# LowduinoSMD.net
KiCad netlist of a schematic drawn in EAGLE
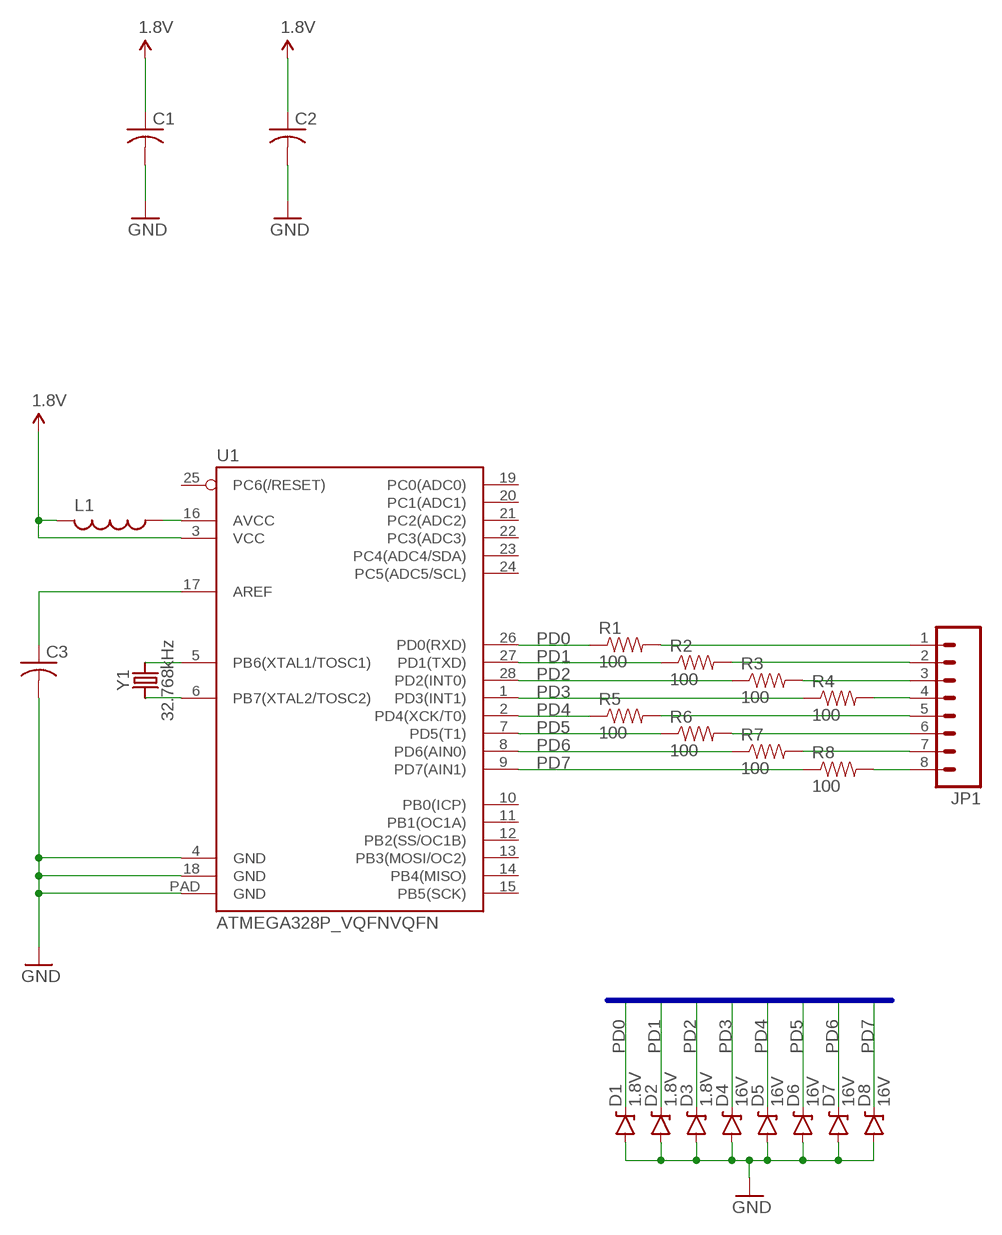
[diagram p0: schematic, sheet 1]

(export (version "E")
  (design (tool "Eeschema 10.0.6"))
  (components
    (comp (ref "C1")
      (value "C-USC0201")
      (footprint "eagle-import:C0201")
      (libsource (lib "eagle-import") (part "C-USC0201"))
    )
    (comp (ref "C2")
      (value "C-USC0402")
      (footprint "eagle-import:C0402")
      (libsource (lib "eagle-import") (part "C-USC0402"))
    )
    (comp (ref "C3")
      (value "C-USC0201")
      (footprint "eagle-import:C0201")
      (libsource (lib "eagle-import") (part "C-USC0201"))
    )
    (comp (ref "D1")
      (value "1.8V")
      (footprint "eagle-import:SOD-123")
      (libsource (lib "eagle-import") (part "DIODE-ZENER16V"))
    )
    (comp (ref "D2")
      (value "1.8V")
      (footprint "eagle-import:SOD-123")
      (libsource (lib "eagle-import") (part "DIODE-ZENER16V"))
    )
    (comp (ref "D3")
      (value "1.8V")
      (footprint "eagle-import:SOD-123")
      (libsource (lib "eagle-import") (part "DIODE-ZENER16V"))
    )
    (comp (ref "D4")
      (value "16V")
      (footprint "eagle-import:SOD-123")
      (libsource (lib "eagle-import") (part "DIODE-ZENER16V"))
    )
    (comp (ref "D5")
      (value "16V")
      (footprint "eagle-import:SOD-123")
      (libsource (lib "eagle-import") (part "DIODE-ZENER16V"))
    )
    (comp (ref "D6")
      (value "16V")
      (footprint "eagle-import:SOD-123")
      (libsource (lib "eagle-import") (part "DIODE-ZENER16V"))
    )
    (comp (ref "D7")
      (value "16V")
      (footprint "eagle-import:SOD-123")
      (libsource (lib "eagle-import") (part "DIODE-ZENER16V"))
    )
    (comp (ref "D8")
      (value "16V")
      (footprint "eagle-import:SOD-123")
      (libsource (lib "eagle-import") (part "DIODE-ZENER16V"))
    )
    (comp (ref "JP1")
      (value "M08SILK_FEMALE_PTH")
      (footprint "eagle-import:1X08")
      (libsource (lib "eagle-import") (part "M08SILK_FEMALE_PTH"))
    )
    (comp (ref "L1")
      (value "L-USL0201")
      (footprint "eagle-import:L0201")
      (libsource (lib "eagle-import") (part "L-USL0201"))
    )
    (comp (ref "R1")
      (value "100")
      (footprint "eagle-import:0603-RES")
      (libsource (lib "eagle-import") (part "100OHM-1/10W-1%(0603)"))
    )
    (comp (ref "R2")
      (value "100")
      (footprint "eagle-import:0603-RES")
      (libsource (lib "eagle-import") (part "100OHM-1/10W-1%(0603)"))
    )
    (comp (ref "R3")
      (value "100")
      (footprint "eagle-import:0603-RES")
      (libsource (lib "eagle-import") (part "100OHM-1/10W-1%(0603)"))
    )
    (comp (ref "R4")
      (value "100")
      (footprint "eagle-import:0603-RES")
      (libsource (lib "eagle-import") (part "100OHM-1/10W-1%(0603)"))
    )
    (comp (ref "R5")
      (value "100")
      (footprint "eagle-import:0603-RES")
      (libsource (lib "eagle-import") (part "100OHM-1/10W-1%(0603)"))
    )
    (comp (ref "R6")
      (value "100")
      (footprint "eagle-import:0603-RES")
      (libsource (lib "eagle-import") (part "100OHM-1/10W-1%(0603)"))
    )
    (comp (ref "R7")
      (value "100")
      (footprint "eagle-import:0603-RES")
      (libsource (lib "eagle-import") (part "100OHM-1/10W-1%(0603)"))
    )
    (comp (ref "R8")
      (value "100")
      (footprint "eagle-import:0603-RES")
      (libsource (lib "eagle-import") (part "100OHM-1/10W-1%(0603)"))
    )
    (comp (ref "U1")
      (value "ATMEGA328P_VQFNVQFN")
      (footprint "eagle-import:VQFN-28")
      (libsource (lib "eagle-import") (part "ATMEGA328P_VQFNVQFN"))
    )
    (comp (ref "Y1")
      (value "32.768kHz")
      (footprint "eagle-import:2-SMD")
      (libsource (lib "eagle-import") (part "FX12232.768KHZ"))
    )
  )
  (nets
    (net (code "1") (name "/PD0") (class "Default")
      (node (ref "D1") (pin "C") (pinfunction "C_C") (pintype "passive"))
      (node (ref "R1") (pin "1") (pinfunction "1_1") (pintype "passive"))
      (node (ref "U1") (pin "26") (pinfunction "PD0(RXD)_26") (pintype "bidirectional"))
    )
    (net (code "2") (name "/PD1") (class "Default")
      (node (ref "D2") (pin "C") (pinfunction "C_C") (pintype "passive"))
      (node (ref "R2") (pin "1") (pinfunction "1_1") (pintype "passive"))
      (node (ref "U1") (pin "27") (pinfunction "PD1(TXD)_27") (pintype "bidirectional"))
    )
    (net (code "3") (name "/PD2") (class "Default")
      (node (ref "D3") (pin "C") (pinfunction "C_C") (pintype "passive"))
      (node (ref "R3") (pin "1") (pinfunction "1_1") (pintype "passive"))
      (node (ref "U1") (pin "28") (pinfunction "PD2(INT0)_28") (pintype "bidirectional"))
    )
    (net (code "4") (name "/PD3") (class "Default")
      (node (ref "D4") (pin "C") (pinfunction "C_C") (pintype "passive"))
      (node (ref "R4") (pin "1") (pinfunction "1_1") (pintype "passive"))
      (node (ref "U1") (pin "1") (pinfunction "PD3(INT1)_1") (pintype "bidirectional"))
    )
    (net (code "5") (name "/PD4") (class "Default")
      (node (ref "D5") (pin "C") (pinfunction "C_C") (pintype "passive"))
      (node (ref "R5") (pin "1") (pinfunction "1_1") (pintype "passive"))
      (node (ref "U1") (pin "2") (pinfunction "PD4(XCK/T0)_2") (pintype "bidirectional"))
    )
    (net (code "6") (name "/PD5") (class "Default")
      (node (ref "D6") (pin "C") (pinfunction "C_C") (pintype "passive"))
      (node (ref "R6") (pin "1") (pinfunction "1_1") (pintype "passive"))
      (node (ref "U1") (pin "7") (pinfunction "PD5(T1)_7") (pintype "bidirectional"))
    )
    (net (code "7") (name "/PD6") (class "Default")
      (node (ref "D7") (pin "C") (pinfunction "C_C") (pintype "passive"))
      (node (ref "R7") (pin "1") (pinfunction "1_1") (pintype "passive"))
      (node (ref "U1") (pin "8") (pinfunction "PD6(AIN0)_8") (pintype "bidirectional"))
    )
    (net (code "8") (name "/PD7") (class "Default")
      (node (ref "D8") (pin "C") (pinfunction "C_C") (pintype "passive"))
      (node (ref "R8") (pin "1") (pinfunction "1_1") (pintype "passive"))
      (node (ref "U1") (pin "9") (pinfunction "PD7(AIN1)_9") (pintype "bidirectional"))
    )
    (net (code "9") (name "1.8V") (class "Default")
      (node (ref "C1") (pin "1") (pinfunction "1_1") (pintype "passive"))
      (node (ref "C2") (pin "1") (pinfunction "1_1") (pintype "passive"))
      (node (ref "L1") (pin "2") (pinfunction "2_2") (pintype "passive"))
      (node (ref "U1") (pin "3") (pinfunction "VCC_3") (pintype "bidirectional"))
    )
    (net (code "10") (name "GND") (class "Default")
      (node (ref "C1") (pin "2") (pinfunction "2_2") (pintype "passive"))
      (node (ref "C2") (pin "2") (pinfunction "2_2") (pintype "passive"))
      (node (ref "C3") (pin "2") (pinfunction "2_2") (pintype "passive"))
      (node (ref "D1") (pin "A") (pinfunction "A_A") (pintype "passive"))
      (node (ref "D2") (pin "A") (pinfunction "A_A") (pintype "passive"))
      (node (ref "D3") (pin "A") (pinfunction "A_A") (pintype "passive"))
      (node (ref "D4") (pin "A") (pinfunction "A_A") (pintype "passive"))
      (node (ref "D5") (pin "A") (pinfunction "A_A") (pintype "passive"))
      (node (ref "D6") (pin "A") (pinfunction "A_A") (pintype "passive"))
      (node (ref "D7") (pin "A") (pinfunction "A_A") (pintype "passive"))
      (node (ref "D8") (pin "A") (pinfunction "A_A") (pintype "passive"))
      (node (ref "U1") (pin "18") (pinfunction "GND_18") (pintype "bidirectional"))
      (node (ref "U1") (pin "4") (pinfunction "GND_4") (pintype "bidirectional"))
      (node (ref "U1") (pin "PAD") (pinfunction "GND_PAD") (pintype "bidirectional"))
    )
    (net (code "11") (name "Net-(JP1-Pad1)") (class "Default")
      (node (ref "JP1") (pin "1") (pinfunction "1_1") (pintype "passive"))
      (node (ref "R1") (pin "2") (pinfunction "2_2") (pintype "passive"))
    )
    (net (code "12") (name "Net-(JP1-Pad2)") (class "Default")
      (node (ref "JP1") (pin "2") (pinfunction "2_2") (pintype "passive"))
      (node (ref "R2") (pin "2") (pinfunction "2_2") (pintype "passive"))
    )
    (net (code "13") (name "Net-(JP1-Pad3)") (class "Default")
      (node (ref "JP1") (pin "3") (pinfunction "3_3") (pintype "passive"))
      (node (ref "R3") (pin "2") (pinfunction "2_2") (pintype "passive"))
    )
    (net (code "14") (name "Net-(JP1-Pad4)") (class "Default")
      (node (ref "JP1") (pin "4") (pinfunction "4_4") (pintype "passive"))
      (node (ref "R4") (pin "2") (pinfunction "2_2") (pintype "passive"))
    )
    (net (code "15") (name "Net-(JP1-Pad5)") (class "Default")
      (node (ref "JP1") (pin "5") (pinfunction "5_5") (pintype "passive"))
      (node (ref "R5") (pin "2") (pinfunction "2_2") (pintype "passive"))
    )
    (net (code "16") (name "Net-(JP1-Pad6)") (class "Default")
      (node (ref "JP1") (pin "6") (pinfunction "6_6") (pintype "passive"))
      (node (ref "R6") (pin "2") (pinfunction "2_2") (pintype "passive"))
    )
    (net (code "17") (name "Net-(JP1-Pad7)") (class "Default")
      (node (ref "JP1") (pin "7") (pinfunction "7_7") (pintype "passive"))
      (node (ref "R7") (pin "2") (pinfunction "2_2") (pintype "passive"))
    )
    (net (code "18") (name "Net-(JP1-Pad8)") (class "Default")
      (node (ref "JP1") (pin "8") (pinfunction "8_8") (pintype "passive"))
      (node (ref "R8") (pin "2") (pinfunction "2_2") (pintype "passive"))
    )
    (net (code "19") (name "Net-(U1-AREF)") (class "Default")
      (node (ref "C3") (pin "1") (pinfunction "1_1") (pintype "passive"))
      (node (ref "U1") (pin "17") (pinfunction "AREF_17") (pintype "bidirectional"))
    )
    (net (code "20") (name "Net-(U1-AVCC)") (class "Default")
      (node (ref "L1") (pin "1") (pinfunction "1_1") (pintype "passive"))
      (node (ref "U1") (pin "16") (pinfunction "AVCC_16") (pintype "bidirectional"))
    )
    (net (code "21") (name "Net-(U1-PB6(XTAL1{slash}TOSC1))") (class "Default")
      (node (ref "U1") (pin "5") (pinfunction "PB6(XTAL1/TOSC1)_5") (pintype "bidirectional"))
      (node (ref "Y1") (pin "2") (pinfunction "2_2") (pintype "passive"))
    )
    (net (code "22") (name "Net-(U1-PB7(XTAL2{slash}TOSC2))") (class "Default")
      (node (ref "U1") (pin "6") (pinfunction "PB7(XTAL2/TOSC2)_6") (pintype "bidirectional"))
      (node (ref "Y1") (pin "1") (pinfunction "1_1") (pintype "passive"))
    )
    (net (code "23") (name "unconnected-(U1-PB0(ICP)-Pad10)") (class "Default")
      (node (ref "U1") (pin "10") (pinfunction "PB0(ICP)_10") (pintype "bidirectional"))
    )
    (net (code "24") (name "unconnected-(U1-PB1(OC1A)-Pad11)") (class "Default")
      (node (ref "U1") (pin "11") (pinfunction "PB1(OC1A)_11") (pintype "bidirectional"))
    )
    (net (code "25") (name "unconnected-(U1-PB2(SS{slash}OC1B)-Pad12)") (class "Default")
      (node (ref "U1") (pin "12") (pinfunction "PB2(SS/OC1B)_12") (pintype "bidirectional"))
    )
    (net (code "26") (name "unconnected-(U1-PB3(MOSI{slash}OC2)-Pad13)") (class "Default")
      (node (ref "U1") (pin "13") (pinfunction "PB3(MOSI/OC2)_13") (pintype "bidirectional"))
    )
    (net (code "27") (name "unconnected-(U1-PB4(MISO)-Pad14)") (class "Default")
      (node (ref "U1") (pin "14") (pinfunction "PB4(MISO)_14") (pintype "bidirectional"))
    )
    (net (code "28") (name "unconnected-(U1-PB5(SCK)-Pad15)") (class "Default")
      (node (ref "U1") (pin "15") (pinfunction "PB5(SCK)_15") (pintype "bidirectional"))
    )
    (net (code "29") (name "unconnected-(U1-PC0(ADC0)-Pad19)") (class "Default")
      (node (ref "U1") (pin "19") (pinfunction "PC0(ADC0)_19") (pintype "bidirectional"))
    )
    (net (code "30") (name "unconnected-(U1-PC1(ADC1)-Pad20)") (class "Default")
      (node (ref "U1") (pin "20") (pinfunction "PC1(ADC1)_20") (pintype "bidirectional"))
    )
    (net (code "31") (name "unconnected-(U1-PC2(ADC2)-Pad21)") (class "Default")
      (node (ref "U1") (pin "21") (pinfunction "PC2(ADC2)_21") (pintype "bidirectional"))
    )
    (net (code "32") (name "unconnected-(U1-PC3(ADC3)-Pad22)") (class "Default")
      (node (ref "U1") (pin "22") (pinfunction "PC3(ADC3)_22") (pintype "bidirectional"))
    )
    (net (code "33") (name "unconnected-(U1-PC4(ADC4{slash}SDA)-Pad23)") (class "Default")
      (node (ref "U1") (pin "23") (pinfunction "PC4(ADC4/SDA)_23") (pintype "bidirectional"))
    )
    (net (code "34") (name "unconnected-(U1-PC5(ADC5{slash}SCL)-Pad24)") (class "Default")
      (node (ref "U1") (pin "24") (pinfunction "PC5(ADC5/SCL)_24") (pintype "bidirectional"))
    )
    (net (code "35") (name "unconnected-(U1-PC6({slash}RESET)-Pad25)") (class "Default")
      (node (ref "U1") (pin "25") (pinfunction "PC6(/RESET)_25") (pintype "bidirectional"))
    )
  )
)
